# PLD_Sail_interface.net
KiCad netlist of a schematic drawn in Altium Designer
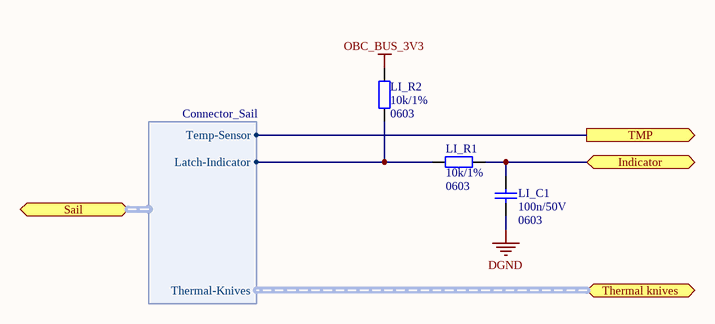
[diagram p0: PLD_Sail_interface.SchDoc]

(export (version "E")
  (design (tool "Eeschema 10.0.6"))
  (components
    (comp (ref "LI_C1")
      (value "100n/50V")
      (footprint "SMD_Capacitor_0603")
      (description "Ceramic Cap Kemet COTS 100n/50V X7R 0603")
      (fields
        (field (name "MANUFACTURER") "Kemet")
        (field (name "MANUFACTURERPARTNUMBER") "C0603T104K5RALTU")
        (field (name "PACKAGE") "0603")
      )
      (libsource (lib "capacitors") (part "Cer_C0603T104K5RALTU"))
    )
    (comp (ref "LI_R1")
      (value "10k/1%")
      (footprint "SMD_Resistor_0603")
      (description "10k/1% Vishay CRCW 0603 Resistor. 100mW, 100ppm, 75V.")
      (fields
        (field (name "MANUFACTURER") "Vishay")
        (field (name "MANUFACTURERPARTNUMBER") "CRCW060310K0FKxxxx")
        (field (name "PACKAGE") "0603")
      )
      (libsource (lib "") (part "CRCW060310K0FKxxxx_1"))
    )
    (comp (ref "LI_R2")
      (value "10k/1%")
      (footprint "SMD_Resistor_0603")
      (description "10k/1% Vishay CRCW 0603 Resistor. 100mW, 100ppm, 75V.")
      (fields
        (field (name "MANUFACTURER") "Vishay")
        (field (name "MANUFACTURERPARTNUMBER") "CRCW060310K0FKxxxx")
        (field (name "PACKAGE") "0603")
      )
      (libsource (lib "resistors") (part "CRCW060310K0FKxxxx"))
    )
  )
  (nets
    (net (code "2") (name "/Indicator") (class "Default")
      (node (ref "LI_C1") (pin "2") (pinfunction "2_2") (pintype "passive"))
      (node (ref "LI_R1") (pin "2") (pinfunction "2_2") (pintype "passive"))
    )
    (net (code "6") (name "DGND") (class "Default")
      (node (ref "LI_C1") (pin "1") (pinfunction "1_1") (pintype "passive"))
    )
    (net (code "7") (name "Net-(LI_R1-Pad1)") (class "Default")
      (node (ref "LI_R1") (pin "1") (pinfunction "1_1") (pintype "passive"))
      (node (ref "LI_R2") (pin "2") (pinfunction "2_2") (pintype "passive"))
    )
    (net (code "8") (name "OBC_BUS_3V3") (class "Default")
      (node (ref "LI_R2") (pin "1") (pinfunction "1_1") (pintype "passive"))
    )
  )
)
